# FrontalKeyboardRGB_-_SCH.net
KiCad netlist of a schematic drawn in Altium Designer
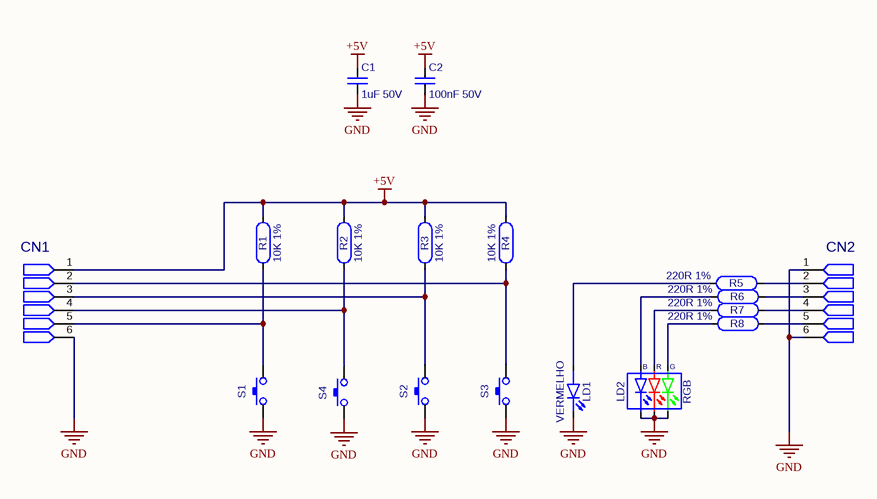
[diagram p0: FrontalKeyboardRGB - SCH.SchDoc]

(export (version "E")
  (design (tool "Eeschema 10.0.6"))
  (components
    (comp (ref "C1")
      (value "1uF 50V")
      (footprint "C0805")
      (libsource (lib "GLOBUS_ALTIUM") (part "CC 1uF 50V 0805"))
    )
    (comp (ref "C2")
      (value "100nF 50V")
      (footprint "C0805")
      (libsource (lib "GLOBUS_ALTIUM") (part "CC 100nF 50V 0805"))
    )
    (comp (ref "CN1")
      (value "CON BARRA 1x6 180 MACHO PTH")
      (footprint "BARRA6PM180")
      (description "Barra de pinos simples 1x6 180g. 2,54mm")
      (fields (field (name "PART NUMBER") "{Part Number}"))
      (libsource (lib "GLOBUS_ALTIUM") (part "CON BARRA 1x6 180 MACHO PTH"))
    )
    (comp (ref "CN2")
      (value "CON BARRA 1x6 180 MACHO PTH")
      (footprint "BARRA6PM180")
      (description "Barra de pinos simples 1x6 180g. 2,54mm")
      (fields (field (name "PART NUMBER") "{Part Number}"))
      (libsource (lib "GLOBUS_ALTIUM") (part "CON BARRA 1x6 180 MACHO PTH"))
    )
    (comp (ref "LD1")
      (value "VERMELHO")
      (footprint "LED3528-RED")
      (description "LED SMT 3528")
      (libsource (lib "GLOBUS_ALTIUM") (part "LED VM 3528"))
    )
    (comp (ref "LD2")
      (value "RGB")
      (footprint "LED-RGB-HL-AF-5060H248BS36FU76GC-S1-T1")
      (description "LED SMT 5060")
      (fields (field (name "PART NUMBER") "HL-AF-5060H248BS36FU76GC-S1-T1"))
      (libsource (lib "GLOBUS_ALTIUM") (part "LED RGB 5060"))
    )
    (comp (ref "R1")
      (value "10K 1%")
      (footprint "R0805")
      (description "RES 10K 1% 0805")
      (fields (field (name "PART NUMBER") "{Part Number}"))
      (libsource (lib "GLOBUS_ALTIUM") (part "RES 10K 1% 0805"))
    )
    (comp (ref "R2")
      (value "10K 1%")
      (footprint "R0805")
      (description "RES 10K 1% 0805")
      (fields (field (name "PART NUMBER") "{Part Number}"))
      (libsource (lib "GLOBUS_ALTIUM") (part "RES 10K 1% 0805"))
    )
    (comp (ref "R3")
      (value "10K 1%")
      (footprint "R0805")
      (description "RES 10K 1% 0805")
      (fields (field (name "PART NUMBER") "{Part Number}"))
      (libsource (lib "GLOBUS_ALTIUM") (part "RES 10K 1% 0805"))
    )
    (comp (ref "R4")
      (value "10K 1%")
      (footprint "R0805")
      (description "RES 10K 1% 0805")
      (fields (field (name "PART NUMBER") "{Part Number}"))
      (libsource (lib "GLOBUS_ALTIUM") (part "RES 10K 1% 0805"))
    )
    (comp (ref "R5")
      (value "220R 1%")
      (footprint "R0805")
      (description "RES 220R 1% 0805")
      (fields (field (name "PART NUMBER") "{Part Number}"))
      (libsource (lib "GLOBUS_ALTIUM") (part "RES 220R 1% 0805"))
    )
    (comp (ref "R6")
      (value "220R 1%")
      (footprint "R0805")
      (description "RES 220R 1% 0805")
      (fields (field (name "PART NUMBER") "{Part Number}"))
      (libsource (lib "GLOBUS_ALTIUM") (part "RES 220R 1% 0805"))
    )
    (comp (ref "R7")
      (value "220R 1%")
      (footprint "R0805")
      (description "RES 220R 1% 0805")
      (fields (field (name "PART NUMBER") "{Part Number}"))
      (libsource (lib "GLOBUS_ALTIUM") (part "RES 220R 1% 0805"))
    )
    (comp (ref "R8")
      (value "220R 1%")
      (footprint "R0805")
      (description "RES 220R 1% 0805")
      (fields (field (name "PART NUMBER") "{Part Number}"))
      (libsource (lib "GLOBUS_ALTIUM") (part "RES 220R 1% 0805"))
    )
    (comp (ref "S1")
      (value "TECLA SMD 4,3mm")
      (footprint "TECLA_TS-06M-ASM")
      (description "TECLA TACTIL 4,3MM SMD")
      (libsource (lib "GLOBUS_ALTIUM") (part "TEC TACTIL 4,3MM SMD"))
    )
    (comp (ref "S2")
      (value "TECLA SMD 4,3mm")
      (footprint "TECLA_TS-06M-ASM")
      (description "TECLA TACTIL 4,3MM SMD")
      (libsource (lib "GLOBUS_ALTIUM") (part "TEC TACTIL 4,3MM SMD"))
    )
    (comp (ref "S3")
      (value "TECLA SMD 4,3mm")
      (footprint "TECLA_TS-06M-ASM")
      (description "TECLA TACTIL 4,3MM SMD")
      (libsource (lib "GLOBUS_ALTIUM") (part "TEC TACTIL 4,3MM SMD"))
    )
    (comp (ref "S4")
      (value "TECLA SMD 4,3mm")
      (footprint "TECLA_TS-06M-ASM")
      (description "TECLA TACTIL 4,3MM SMD")
      (libsource (lib "GLOBUS_ALTIUM") (part "TEC TACTIL 4,3MM SMD"))
    )
  )
  (nets
    (net (code "1") (name "+5V") (class "Default")
      (node (ref "C1") (pin "1") (pinfunction "1_1") (pintype "passive"))
      (node (ref "C2") (pin "1") (pinfunction "1_1") (pintype "passive"))
      (node (ref "CN1") (pin "1") (pinfunction "1_1") (pintype "passive"))
      (node (ref "R1") (pin "1") (pinfunction "1_1") (pintype "passive"))
      (node (ref "R2") (pin "1") (pinfunction "1_1") (pintype "passive"))
      (node (ref "R3") (pin "1") (pinfunction "1_1") (pintype "passive"))
      (node (ref "R4") (pin "2") (pinfunction "2_2") (pintype "passive"))
    )
    (net (code "2") (name "GND") (class "Default")
      (node (ref "C1") (pin "2") (pinfunction "2_2") (pintype "passive"))
      (node (ref "C2") (pin "2") (pinfunction "2_2") (pintype "passive"))
      (node (ref "CN1") (pin "6") (pinfunction "6_6") (pintype "passive"))
      (node (ref "CN2") (pin "1") (pinfunction "1_1") (pintype "passive"))
      (node (ref "CN2") (pin "6") (pinfunction "6_6") (pintype "passive"))
      (node (ref "LD1") (pin "2") (pinfunction "cathode_2") (pintype "passive"))
      (node (ref "LD2") (pin "4") (pinfunction "cathode_4") (pintype "passive"))
      (node (ref "LD2") (pin "5") (pinfunction "cathode_5") (pintype "passive"))
      (node (ref "LD2") (pin "6") (pinfunction "cathode_6") (pintype "passive"))
      (node (ref "S1") (pin "2") (pinfunction "2_2") (pintype "passive"))
      (node (ref "S2") (pin "2") (pinfunction "2_2") (pintype "passive"))
      (node (ref "S3") (pin "2") (pinfunction "2_2") (pintype "passive"))
      (node (ref "S4") (pin "2") (pinfunction "2_2") (pintype "passive"))
    )
    (net (code "3") (name "Net-(CN1-Pad2)") (class "Default")
      (node (ref "CN1") (pin "2") (pinfunction "2_2") (pintype "passive"))
      (node (ref "R4") (pin "1") (pinfunction "1_1") (pintype "passive"))
      (node (ref "S3") (pin "1") (pinfunction "1_1") (pintype "passive"))
    )
    (net (code "4") (name "Net-(CN1-Pad3)") (class "Default")
      (node (ref "CN1") (pin "3") (pinfunction "3_3") (pintype "passive"))
      (node (ref "R3") (pin "2") (pinfunction "2_2") (pintype "passive"))
      (node (ref "S2") (pin "1") (pinfunction "1_1") (pintype "passive"))
    )
    (net (code "5") (name "Net-(CN1-Pad4)") (class "Default")
      (node (ref "CN1") (pin "4") (pinfunction "4_4") (pintype "passive"))
      (node (ref "R2") (pin "2") (pinfunction "2_2") (pintype "passive"))
      (node (ref "S4") (pin "1") (pinfunction "1_1") (pintype "passive"))
    )
    (net (code "6") (name "Net-(CN1-Pad5)") (class "Default")
      (node (ref "CN1") (pin "5") (pinfunction "5_5") (pintype "passive"))
      (node (ref "R1") (pin "2") (pinfunction "2_2") (pintype "passive"))
      (node (ref "S1") (pin "1") (pinfunction "1_1") (pintype "passive"))
    )
    (net (code "7") (name "Net-(CN2-Pad2)") (class "Default")
      (node (ref "CN2") (pin "2") (pinfunction "2_2") (pintype "passive"))
      (node (ref "R5") (pin "2") (pinfunction "2_2") (pintype "passive"))
    )
    (net (code "8") (name "Net-(CN2-Pad3)") (class "Default")
      (node (ref "CN2") (pin "3") (pinfunction "3_3") (pintype "passive"))
      (node (ref "R6") (pin "2") (pinfunction "2_2") (pintype "passive"))
    )
    (net (code "9") (name "Net-(CN2-Pad4)") (class "Default")
      (node (ref "CN2") (pin "4") (pinfunction "4_4") (pintype "passive"))
      (node (ref "R7") (pin "2") (pinfunction "2_2") (pintype "passive"))
    )
    (net (code "10") (name "Net-(CN2-Pad5)") (class "Default")
      (node (ref "CN2") (pin "5") (pinfunction "5_5") (pintype "passive"))
      (node (ref "R8") (pin "2") (pinfunction "2_2") (pintype "passive"))
    )
    (net (code "11") (name "Net-(LD1-anode)") (class "Default")
      (node (ref "LD1") (pin "1") (pinfunction "anode_1") (pintype "passive"))
      (node (ref "R5") (pin "1") (pinfunction "1_1") (pintype "passive"))
    )
    (net (code "12") (name "Net-(LD2-anode-Pad1)") (class "Default")
      (node (ref "LD2") (pin "1") (pinfunction "anode_1") (pintype "passive"))
      (node (ref "R8") (pin "1") (pinfunction "1_1") (pintype "passive"))
    )
    (net (code "13") (name "Net-(LD2-anode-Pad2)") (class "Default")
      (node (ref "LD2") (pin "2") (pinfunction "anode_2") (pintype "passive"))
      (node (ref "R7") (pin "1") (pinfunction "1_1") (pintype "passive"))
    )
    (net (code "14") (name "Net-(LD2-anode-Pad3)") (class "Default")
      (node (ref "LD2") (pin "3") (pinfunction "anode_3") (pintype "passive"))
      (node (ref "R6") (pin "1") (pinfunction "1_1") (pintype "passive"))
    )
  )
)
